# Main.net
KiCad netlist of a schematic drawn in Altium Designer
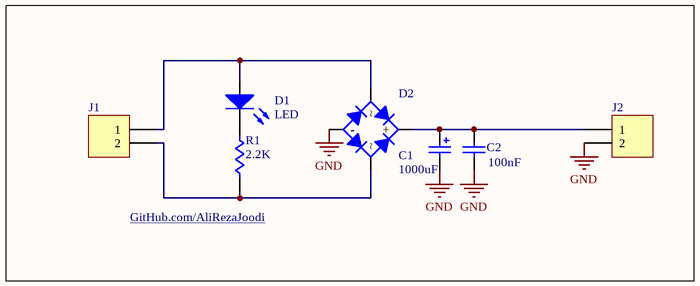
[diagram p0: Main.SchDoc]

(export (version "E")
  (design (tool "Eeschema 10.0.6"))
  (components
    (comp (ref "C1")
      (value "1000uF")
      (footprint "CAPPR5-10x5")
      (description "Polarized Capacitor (Radial)")
      (fields
        (field (name "MANUFACTURER") "Generic Components")
        (field (name "Comment") "Cap Pol1")
        (field (name "PUBLISHER") "Altium Limited")
      )
      (libsource (lib "Miscellaneous Devices") (part "Cap Pol1"))
    )
    (comp (ref "C2")
      (value "100nF")
      (footprint "CAPNTO2.54-3.05x1.78A")
      (description "Capacitor")
      (fields
        (field (name "MANUFACTURER") "Generic Components")
        (field (name "Comment") "Cap")
        (field (name "PUBLISHER") "Altium Limited")
      )
      (libsource (lib "Miscellaneous Devices") (part "Cap"))
    )
    (comp (ref "D1")
      (value "LED")
      (footprint "LED-5mm_Red")
      (description "Typical INFRARED GaAs LED")
      (fields (field (name "MANUFACTURER") "Generic Components") (field (name "PUBLISHER") "Altium Limited"))
      (libsource (lib "Miscellaneous Devices") (part "LED"))
    )
    (comp (ref "D2")
      (value "Bridge1")
      (footprint "BRIDGE-1")
      (description "Full Wave Diode Bridge")
      (fields (field (name "MANUFACTURER") "Generic Components") (field (name "PUBLISHER") "Altium Limited"))
      (libsource (lib "Miscellaneous Devices") (part "Bridge1"))
    )
    (comp (ref "J1")
      (value "Header 2")
      (footprint "W2312R5MILH - duplicate")
      (description "Header, 2-Pin")
      (fields (field (name "PUBLISHER") "Altium Limited"))
      (libsource (lib "Miscellaneous Connectors") (part "Header 2"))
    )
    (comp (ref "J2")
      (value "Header 2")
      (footprint "W2312R5MILH - duplicate")
      (description "Header, 2-Pin")
      (fields (field (name "PUBLISHER") "Altium Limited"))
      (libsource (lib "") (part "Header 2_1"))
    )
    (comp (ref "R1")
      (value "2.2K")
      (footprint "AXIAL-0.4")
      (description "Resistor")
      (fields
        (field (name "MANUFACTURER") "Generic Components")
        (field (name "Comment") "Res1")
        (field (name "PUBLISHER") "Altium Limited")
      )
      (libsource (lib "Miscellaneous Devices") (part "Res1"))
    )
  )
  (nets
    (net (code "1") (name "GND") (class "Default")
      (node (ref "C1") (pin "2") (pinfunction "2_2") (pintype "passive"))
      (node (ref "C2") (pin "1") (pinfunction "1_1") (pintype "passive"))
      (node (ref "D2") (pin "1") (pinfunction "-_1") (pintype "passive"))
      (node (ref "J2") (pin "2") (pinfunction "2_2") (pintype "passive"))
    )
    (net (code "2") (name "Net-(D1-A)") (class "Default")
      (node (ref "D1") (pin "1") (pinfunction "A_1") (pintype "passive"))
      (node (ref "D2") (pin "2") (pinfunction "~_2") (pintype "passive"))
      (node (ref "J1") (pin "1") (pinfunction "1_1") (pintype "passive"))
    )
    (net (code "3") (name "Net-(D1-K)") (class "Default")
      (node (ref "D1") (pin "2") (pinfunction "K_2") (pintype "passive"))
      (node (ref "R1") (pin "1") (pinfunction "1_1") (pintype "passive"))
    )
    (net (code "4") (name "Net-(D2-+)") (class "Default")
      (node (ref "C1") (pin "1") (pinfunction "1_1") (pintype "passive"))
      (node (ref "C2") (pin "2") (pinfunction "2_2") (pintype "passive"))
      (node (ref "D2") (pin "3") (pinfunction "+_3") (pintype "passive"))
      (node (ref "J2") (pin "1") (pinfunction "1_1") (pintype "passive"))
    )
    (net (code "5") (name "Net-(D2-~-Pad4)") (class "Default")
      (node (ref "D2") (pin "4") (pinfunction "~_4") (pintype "passive"))
      (node (ref "J1") (pin "2") (pinfunction "2_2") (pintype "passive"))
      (node (ref "R1") (pin "2") (pinfunction "2_2") (pintype "passive"))
    )
  )
)
